# RobotControlBoard.net
KiCad netlist of a schematic drawn in EAGLE
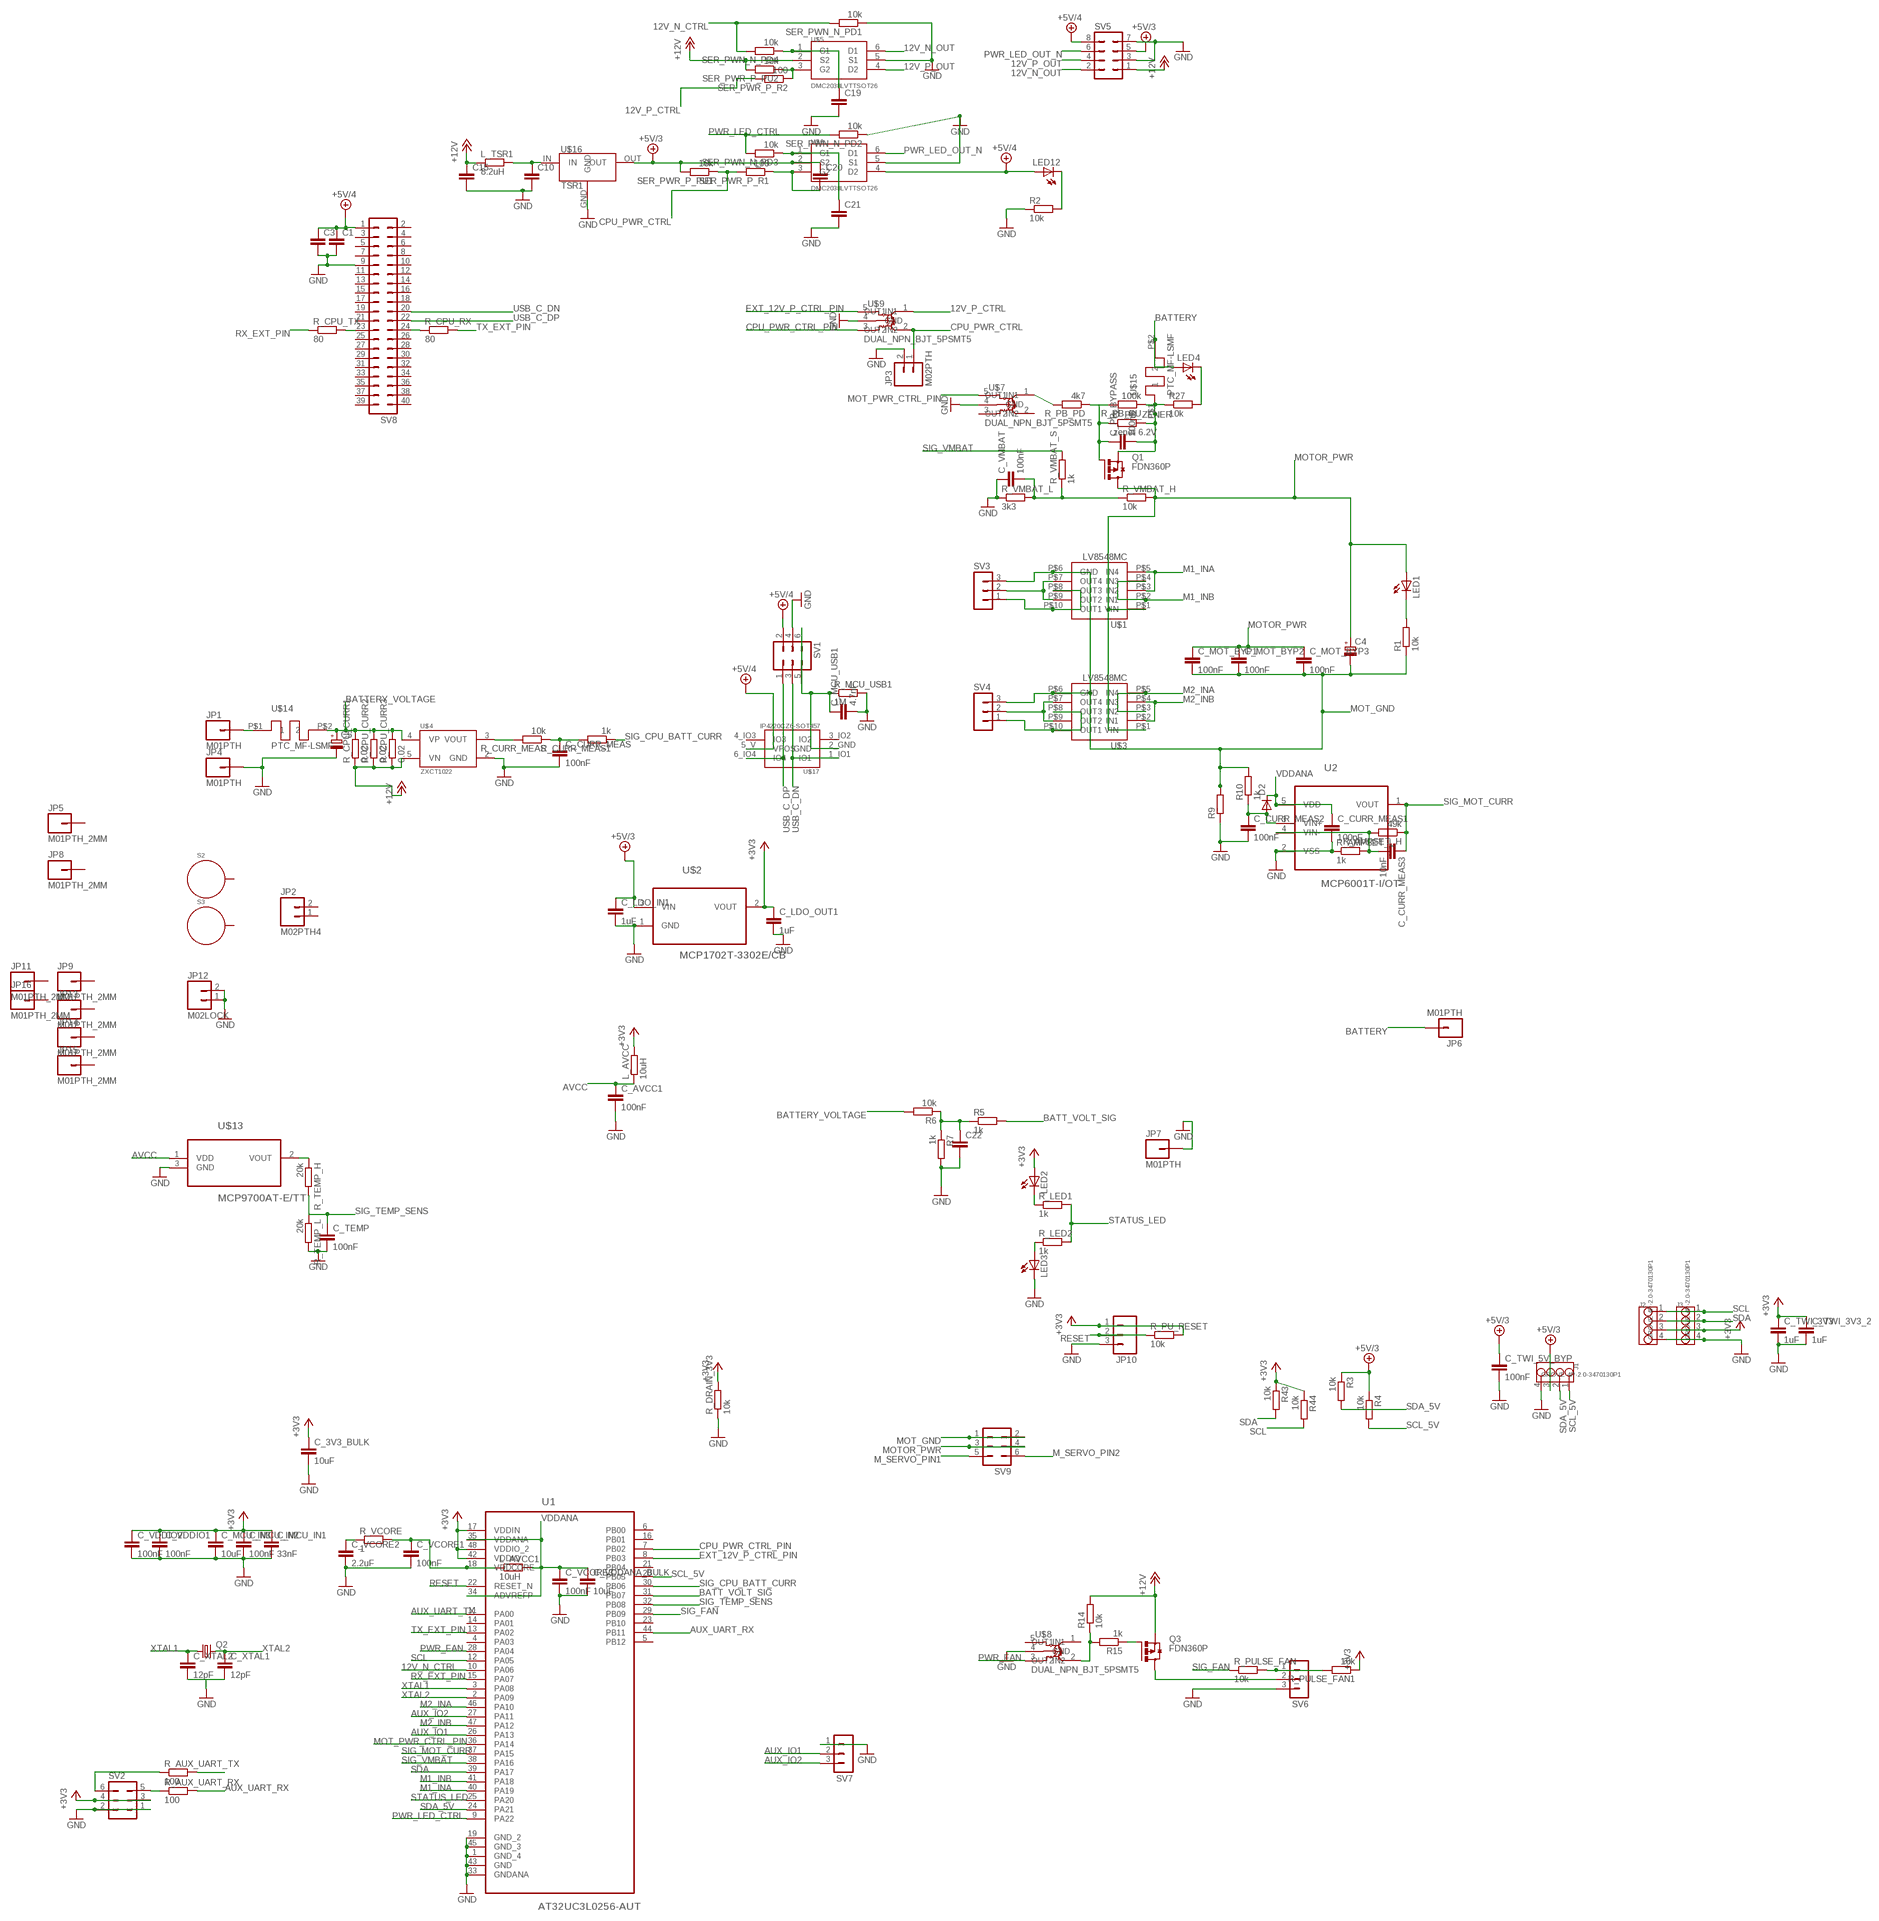
[diagram p0: schematic, sheet 1]

(export (version "E")
  (design (tool "Eeschema 10.0.6"))
  (components
    (comp (ref "C1")
      (value "C-EUC1210K")
      (footprint "eagle-import:C1210K")
      (libsource (lib "eagle-import") (part "C-EUC1210K"))
    )
    (comp (ref "C3")
      (value "C-EUC1210K")
      (footprint "eagle-import:C1210K")
      (libsource (lib "eagle-import") (part "C-EUC1210K"))
    )
    (comp (ref "C4")
      (value "CPOL-EUE3.5-8")
      (footprint "eagle-import:E3,5-8")
      (libsource (lib "eagle-import") (part "CPOL-EUE3.5-8"))
    )
    (comp (ref "C5")
      (value "CPOL-EUE2.5-6")
      (footprint "eagle-import:E2,5-6")
      (libsource (lib "eagle-import") (part "CPOL-EUE2.5-6"))
    )
    (comp (ref "C10")
      (value "C-EUC0805")
      (footprint "eagle-import:C0805")
      (libsource (lib "eagle-import") (part "C-EUC0805"))
    )
    (comp (ref "C15")
      (value "C-EUC0805")
      (footprint "eagle-import:C0805")
      (libsource (lib "eagle-import") (part "C-EUC0805"))
    )
    (comp (ref "C19")
      (value "C-EUC0603K")
      (footprint "eagle-import:C0603K")
      (libsource (lib "eagle-import") (part "C-EUC0603K"))
    )
    (comp (ref "C20")
      (value "C-EUC0603K")
      (footprint "eagle-import:C0603K")
      (libsource (lib "eagle-import") (part "C-EUC0603K"))
    )
    (comp (ref "C21")
      (value "C-EUC0603K")
      (footprint "eagle-import:C0603K")
      (libsource (lib "eagle-import") (part "C-EUC0603K"))
    )
    (comp (ref "C22")
      (value "C-EUC0603K")
      (footprint "eagle-import:C0603K")
      (libsource (lib "eagle-import") (part "C-EUC0603K"))
    )
    (comp (ref "C_3V3_BULK")
      (value "10uF")
      (footprint "eagle-import:C1206")
      (libsource (lib "eagle-import") (part "C-EUC1206"))
    )
    (comp (ref "C_AVCC1")
      (value "100nF")
      (footprint "eagle-import:C0603")
      (libsource (lib "eagle-import") (part "C-EUC0603"))
    )
    (comp (ref "C_CURR_MEAS")
      (value "100nF")
      (footprint "eagle-import:C0603K")
      (libsource (lib "eagle-import") (part "C-EUC0603K"))
    )
    (comp (ref "C_CURR_MEAS1")
      (value "100nF")
      (footprint "eagle-import:C0603K")
      (libsource (lib "eagle-import") (part "C-EUC0603K"))
    )
    (comp (ref "C_CURR_MEAS2")
      (value "100nF")
      (footprint "eagle-import:C0603K")
      (libsource (lib "eagle-import") (part "C-EUC0603K"))
    )
    (comp (ref "C_CURR_MEAS3")
      (value "10nF")
      (footprint "eagle-import:C0603K")
      (libsource (lib "eagle-import") (part "C-EUC0603K"))
    )
    (comp (ref "C_LDO_IN1")
      (value "1uF")
      (footprint "eagle-import:C0805")
      (libsource (lib "eagle-import") (part "C-EUC0805"))
    )
    (comp (ref "C_LDO_OUT1")
      (value "1uF")
      (footprint "eagle-import:C0805")
      (libsource (lib "eagle-import") (part "C-EUC0805"))
    )
    (comp (ref "C_MCU_IN1")
      (value "33nF")
      (footprint "eagle-import:C0603K")
      (libsource (lib "eagle-import") (part "C-EUC0603K"))
    )
    (comp (ref "C_MCU_IN2")
      (value "100nF")
      (footprint "eagle-import:C0603K")
      (libsource (lib "eagle-import") (part "C-EUC0603K"))
    )
    (comp (ref "C_MCU_IN3")
      (value "10uF")
      (footprint "eagle-import:C0805")
      (libsource (lib "eagle-import") (part "C-EUC0805"))
    )
    (comp (ref "C_MCU_USB1")
      (value "4.7nF")
      (footprint "eagle-import:C0603")
      (libsource (lib "eagle-import") (part "C-EUC0603"))
    )
    (comp (ref "C_MOT_BYP1")
      (value "100nF")
      (footprint "eagle-import:C0603K")
      (libsource (lib "eagle-import") (part "C-EUC0603K"))
    )
    (comp (ref "C_MOT_BYP2")
      (value "100nF")
      (footprint "eagle-import:C0603K")
      (libsource (lib "eagle-import") (part "C-EUC0603K"))
    )
    (comp (ref "C_MOT_BYP3")
      (value "100nF")
      (footprint "eagle-import:C0603K")
      (libsource (lib "eagle-import") (part "C-EUC0603K"))
    )
    (comp (ref "C_PB_BYPASS")
      (value "100nF")
      (footprint "eagle-import:C0603K")
      (libsource (lib "eagle-import") (part "C-EUC0603K"))
    )
    (comp (ref "C_TEMP")
      (value "100nF")
      (footprint "eagle-import:C0603")
      (libsource (lib "eagle-import") (part "C-EUC0603"))
    )
    (comp (ref "C_TWI_3V3")
      (value "1uF")
      (footprint "eagle-import:C0805K")
      (libsource (lib "eagle-import") (part "C-EUC0805K"))
    )
    (comp (ref "C_TWI_3V3_2")
      (value "1uF")
      (footprint "eagle-import:C0805K")
      (libsource (lib "eagle-import") (part "C-EUC0805K"))
    )
    (comp (ref "C_TWI_5V_BYP")
      (value "100nF")
      (footprint "eagle-import:C0603K")
      (libsource (lib "eagle-import") (part "C-EUC0603K"))
    )
    (comp (ref "C_VCORE1")
      (value "100nF")
      (footprint "eagle-import:C0603K")
      (libsource (lib "eagle-import") (part "C-EUC0603K"))
    )
    (comp (ref "C_VCORE2")
      (value "2.2uF")
      (footprint "eagle-import:C0805")
      (libsource (lib "eagle-import") (part "C-EUC0805"))
    )
    (comp (ref "C_VCORE3")
      (value "100nF")
      (footprint "eagle-import:C0603K")
      (libsource (lib "eagle-import") (part "C-EUC0603K"))
    )
    (comp (ref "C_VDDANA_BULK")
      (value "10uF")
      (footprint "eagle-import:C0805")
      (libsource (lib "eagle-import") (part "C-EUC0805"))
    )
    (comp (ref "C_VDDIO1")
      (value "100nF")
      (footprint "eagle-import:C0603K")
      (libsource (lib "eagle-import") (part "C-EUC0603K"))
    )
    (comp (ref "C_VDDIO2")
      (value "100nF")
      (footprint "eagle-import:C0603K")
      (libsource (lib "eagle-import") (part "C-EUC0603K"))
    )
    (comp (ref "C_VMBAT")
      (value "100nF")
      (footprint "eagle-import:C0603K")
      (libsource (lib "eagle-import") (part "C-EUC0603K"))
    )
    (comp (ref "C_XTAL1")
      (value "12pF")
      (footprint "eagle-import:C0603K")
      (libsource (lib "eagle-import") (part "C-EUC0603K"))
    )
    (comp (ref "C_XTAL2")
      (value "12pF")
      (footprint "eagle-import:C0603K")
      (libsource (lib "eagle-import") (part "C-EUC0603K"))
    )
    (comp (ref "D2")
      (value "DIODE-SOD323-W")
      (footprint "eagle-import:SOD323-W")
      (libsource (lib "eagle-import") (part "DIODE-SOD323-W"))
    )
    (comp (ref "D_PB_ZENER")
      (value "zener 6.2V")
      (footprint "eagle-import:R0805W")
      (libsource (lib "eagle-import") (part "R-EU_R0805W"))
    )
    (comp (ref "J1")
      (value "GROVE-4P-2.0-3470130P1")
      (footprint "eagle-import:4P-2.0")
      (libsource (lib "eagle-import") (part "GROVE-4P-2.0-3470130P1"))
    )
    (comp (ref "J2")
      (value "GROVE-4P-2.0-3470130P1")
      (footprint "eagle-import:4P-2.0")
      (libsource (lib "eagle-import") (part "GROVE-4P-2.0-3470130P1"))
    )
    (comp (ref "J3")
      (value "GROVE-4P-2.0-3470130P1")
      (footprint "eagle-import:4P-2.0")
      (libsource (lib "eagle-import") (part "GROVE-4P-2.0-3470130P1"))
    )
    (comp (ref "JP1")
      (value "M01PTH")
      (footprint "eagle-import:1X01")
      (libsource (lib "eagle-import") (part "M01PTH"))
    )
    (comp (ref "JP2")
      (value "M02PTH4")
      (footprint "eagle-import:1X02_XTRA_BIG")
      (libsource (lib "eagle-import") (part "M02PTH4"))
    )
    (comp (ref "JP3")
      (value "M02PTH")
      (footprint "eagle-import:1X02")
      (libsource (lib "eagle-import") (part "M02PTH"))
    )
    (comp (ref "JP4")
      (value "M01PTH")
      (footprint "eagle-import:1X01")
      (libsource (lib "eagle-import") (part "M01PTH"))
    )
    (comp (ref "JP5")
      (value "M01PTH_2MM")
      (footprint "eagle-import:1X01_2MM")
      (libsource (lib "eagle-import") (part "M01PTH_2MM"))
    )
    (comp (ref "JP6")
      (value "M01PTH")
      (footprint "eagle-import:1X01")
      (libsource (lib "eagle-import") (part "M01PTH"))
    )
    (comp (ref "JP7")
      (value "M01PTH")
      (footprint "eagle-import:1X01")
      (libsource (lib "eagle-import") (part "M01PTH"))
    )
    (comp (ref "JP8")
      (value "M01PTH_2MM")
      (footprint "eagle-import:1X01_2MM")
      (libsource (lib "eagle-import") (part "M01PTH_2MM"))
    )
    (comp (ref "JP9")
      (value "M01PTH_2MM")
      (footprint "eagle-import:1X01_2MM")
      (libsource (lib "eagle-import") (part "M01PTH_2MM"))
    )
    (comp (ref "JP10")
      (value "M03PTH")
      (footprint "eagle-import:1X03")
      (libsource (lib "eagle-import") (part "M03PTH"))
    )
    (comp (ref "JP11")
      (value "M01PTH_2MM")
      (footprint "eagle-import:1X01_2MM")
      (libsource (lib "eagle-import") (part "M01PTH_2MM"))
    )
    (comp (ref "JP12")
      (value "M02LOCK")
      (footprint "eagle-import:1X02_LOCK")
      (libsource (lib "eagle-import") (part "M02LOCK"))
    )
    (comp (ref "JP13")
      (value "M01PTH_2MM")
      (footprint "eagle-import:1X01_2MM")
      (libsource (lib "eagle-import") (part "M01PTH_2MM"))
    )
    (comp (ref "JP14")
      (value "M01PTH_2MM")
      (footprint "eagle-import:1X01_2MM")
      (libsource (lib "eagle-import") (part "M01PTH_2MM"))
    )
    (comp (ref "JP15")
      (value "M01PTH_2MM")
      (footprint "eagle-import:1X01_2MM")
      (libsource (lib "eagle-import") (part "M01PTH_2MM"))
    )
    (comp (ref "JP16")
      (value "M01PTH_2MM")
      (footprint "eagle-import:1X01_2MM")
      (libsource (lib "eagle-import") (part "M01PTH_2MM"))
    )
    (comp (ref "LED1")
      (value "LEDSML0603")
      (footprint "eagle-import:SML0603")
      (libsource (lib "eagle-import") (part "LEDSML0603"))
    )
    (comp (ref "LED2")
      (value "LEDSML0603")
      (footprint "eagle-import:SML0603")
      (libsource (lib "eagle-import") (part "LEDSML0603"))
    )
    (comp (ref "LED3")
      (value "LEDSML0603")
      (footprint "eagle-import:SML0603")
      (libsource (lib "eagle-import") (part "LEDSML0603"))
    )
    (comp (ref "LED4")
      (value "LEDSML0603")
      (footprint "eagle-import:SML0603")
      (libsource (lib "eagle-import") (part "LEDSML0603"))
    )
    (comp (ref "LED12")
      (value "LEDSML0603")
      (footprint "eagle-import:SML0603")
      (libsource (lib "eagle-import") (part "LEDSML0603"))
    )
    (comp (ref "L_AVCC")
      (value "10uH")
      (footprint "eagle-import:R0603")
      (libsource (lib "eagle-import") (part "R-EU_R0603"))
    )
    (comp (ref "L_AVCC1")
      (value "10uH")
      (footprint "eagle-import:R0805")
      (libsource (lib "eagle-import") (part "R-EU_R0805"))
    )
    (comp (ref "L_TSR1")
      (value "8.2uH")
      (footprint "eagle-import:M0805")
      (libsource (lib "eagle-import") (part "R-EU_M0805"))
    )
    (comp (ref "Q1")
      (value "FDN360P")
      (footprint "eagle-import:SUPER-SOT3")
      (libsource (lib "eagle-import") (part "FDN360P"))
    )
    (comp (ref "Q2")
      (value "CRYSTALHC49S")
      (footprint "eagle-import:HC49_S")
      (libsource (lib "eagle-import") (part "CRYSTALHC49S"))
    )
    (comp (ref "Q3")
      (value "FDN360P")
      (footprint "eagle-import:SUPER-SOT3")
      (libsource (lib "eagle-import") (part "FDN360P"))
    )
    (comp (ref "R1")
      (value "10k")
      (footprint "eagle-import:R0603")
      (libsource (lib "eagle-import") (part "R-EU_R0603"))
    )
    (comp (ref "R2")
      (value "10k")
      (footprint "eagle-import:R0603")
      (libsource (lib "eagle-import") (part "R-EU_R0603"))
    )
    (comp (ref "R3")
      (value "10k")
      (footprint "eagle-import:R0603")
      (libsource (lib "eagle-import") (part "R-EU_R0603"))
    )
    (comp (ref "R4")
      (value "10k")
      (footprint "eagle-import:R0603")
      (libsource (lib "eagle-import") (part "R-EU_R0603"))
    )
    (comp (ref "R5")
      (value "1k")
      (footprint "eagle-import:R0603")
      (libsource (lib "eagle-import") (part "R-EU_R0603"))
    )
    (comp (ref "R6")
      (value "10k")
      (footprint "eagle-import:R0603")
      (libsource (lib "eagle-import") (part "R-EU_R0603"))
    )
    (comp (ref "R7")
      (value "1k")
      (footprint "eagle-import:R0603")
      (libsource (lib "eagle-import") (part "R-EU_R0603"))
    )
    (comp (ref "R9")
      (value "R-EU_M1206")
      (footprint "eagle-import:M1206")
      (libsource (lib "eagle-import") (part "R-EU_M1206"))
    )
    (comp (ref "R10")
      (value "1k")
      (footprint "eagle-import:R0603")
      (libsource (lib "eagle-import") (part "R-EU_R0603"))
    )
    (comp (ref "R14")
      (value "10k")
      (footprint "eagle-import:R0603")
      (libsource (lib "eagle-import") (part "R-EU_R0603"))
    )
    (comp (ref "R15")
      (value "1k")
      (footprint "eagle-import:R0603")
      (libsource (lib "eagle-import") (part "R-EU_R0603"))
    )
    (comp (ref "R27")
      (value "10k")
      (footprint "eagle-import:R0603")
      (libsource (lib "eagle-import") (part "R-EU_R0603"))
    )
    (comp (ref "R43")
      (value "10k")
      (footprint "eagle-import:R0603")
      (libsource (lib "eagle-import") (part "R-EU_R0603"))
    )
    (comp (ref "R44")
      (value "10k")
      (footprint "eagle-import:R0603")
      (libsource (lib "eagle-import") (part "R-EU_R0603"))
    )
    (comp (ref "R_AMPSET_H")
      (value "49k")
      (footprint "eagle-import:R0603")
      (libsource (lib "eagle-import") (part "R-EU_R0603"))
    )
    (comp (ref "R_AMPSET_L")
      (value "1k")
      (footprint "eagle-import:R0603")
      (libsource (lib "eagle-import") (part "R-EU_R0603"))
    )
    (comp (ref "R_AUX_UART_RX")
      (value "100")
      (footprint "eagle-import:R0603")
      (libsource (lib "eagle-import") (part "R-EU_R0603"))
    )
    (comp (ref "R_AUX_UART_TX")
      (value "100")
      (footprint "eagle-import:R0603")
      (libsource (lib "eagle-import") (part "R-EU_R0603"))
    )
    (comp (ref "R_CPU_CURR1")
      (value "0.02")
      (footprint "eagle-import:R0805")
      (libsource (lib "eagle-import") (part "R-EU_R0805"))
    )
    (comp (ref "R_CPU_CURR2")
      (value "0.02")
      (footprint "eagle-import:R0805")
      (libsource (lib "eagle-import") (part "R-EU_R0805"))
    )
    (comp (ref "R_CPU_CURR3")
      (value "0.02")
      (footprint "eagle-import:R0805")
      (libsource (lib "eagle-import") (part "R-EU_R0805"))
    )
    (comp (ref "R_CPU_RX")
      (value "80")
      (footprint "eagle-import:R0603")
      (libsource (lib "eagle-import") (part "R-EU_R0603"))
    )
    (comp (ref "R_CPU_TX")
      (value "80")
      (footprint "eagle-import:R0603")
      (libsource (lib "eagle-import") (part "R-EU_R0603"))
    )
    (comp (ref "R_CURR_MEAS")
      (value "10k")
      (footprint "eagle-import:R0603")
      (libsource (lib "eagle-import") (part "R-EU_R0603"))
    )
    (comp (ref "R_CURR_MEAS1")
      (value "1k")
      (footprint "eagle-import:R0603")
      (libsource (lib "eagle-import") (part "R-EU_R0603"))
    )
    (comp (ref "R_DRAIN_3V3")
      (value "10k")
      (footprint "eagle-import:R0603")
      (libsource (lib "eagle-import") (part "R-EU_R0603"))
    )
    (comp (ref "R_LED1")
      (value "1k")
      (footprint "eagle-import:R0603")
      (libsource (lib "eagle-import") (part "R-EU_R0603"))
    )
    (comp (ref "R_LED2")
      (value "1k")
      (footprint "eagle-import:R0603")
      (libsource (lib "eagle-import") (part "R-EU_R0603"))
    )
    (comp (ref "R_MCU_USB1")
      (value "1M")
      (footprint "eagle-import:R0603")
      (libsource (lib "eagle-import") (part "R-EU_R0603"))
    )
    (comp (ref "R_PB_PD")
      (value "4k7")
      (footprint "eagle-import:R0603")
      (libsource (lib "eagle-import") (part "R-EU_R0603"))
    )
    (comp (ref "R_PB_PU")
      (value "100k")
      (footprint "eagle-import:R0603")
      (libsource (lib "eagle-import") (part "R-EU_R0603"))
    )
    (comp (ref "R_PULSE_FAN")
      (value "10k")
      (footprint "eagle-import:R0603")
      (libsource (lib "eagle-import") (part "R-EU_R0603"))
    )
    (comp (ref "R_PULSE_FAN1")
      (value "10k")
      (footprint "eagle-import:R0603")
      (libsource (lib "eagle-import") (part "R-EU_R0603"))
    )
    (comp (ref "R_PU_RESET")
      (value "10k")
      (footprint "eagle-import:R0603")
      (libsource (lib "eagle-import") (part "R-EU_R0603"))
    )
    (comp (ref "R_TEMP_H")
      (value "20k")
      (footprint "eagle-import:R0603")
      (libsource (lib "eagle-import") (part "R-EU_R0603"))
    )
    (comp (ref "R_TEMP_L")
      (value "20k")
      (footprint "eagle-import:R0603")
      (libsource (lib "eagle-import") (part "R-EU_R0603"))
    )
    (comp (ref "R_VCORE")
      (value "1")
      (footprint "eagle-import:R0603")
      (libsource (lib "eagle-import") (part "R-EU_R0603"))
    )
    (comp (ref "R_VMBAT_H")
      (value "10k")
      (footprint "eagle-import:R0603")
      (libsource (lib "eagle-import") (part "R-EU_R0603"))
    )
    (comp (ref "R_VMBAT_L")
      (value "3k3")
      (footprint "eagle-import:R0603")
      (libsource (lib "eagle-import") (part "R-EU_R0603"))
    )
    (comp (ref "R_VMBAT_S")
      (value "1k")
      (footprint "eagle-import:R0603")
      (libsource (lib "eagle-import") (part "R-EU_R0603"))
    )
    (comp (ref "S2")
      (value "STANDOFF_ELECTRICAL")
      (footprint "eagle-import:STANDOFF-ELECTRICAL")
      (libsource (lib "eagle-import") (part "STANDOFF_ELECTRICAL"))
    )
    (comp (ref "S3")
      (value "STANDOFF_ELECTRICAL")
      (footprint "eagle-import:STANDOFF-ELECTRICAL")
      (libsource (lib "eagle-import") (part "STANDOFF_ELECTRICAL"))
    )
    (comp (ref "SER_PWN_N_PD1")
      (value "10k")
      (footprint "eagle-import:R0603")
      (libsource (lib "eagle-import") (part "R-EU_R0603"))
    )
    (comp (ref "SER_PWN_N_PD2")
      (value "10k")
      (footprint "eagle-import:R0603")
      (libsource (lib "eagle-import") (part "R-EU_R0603"))
    )
    (comp (ref "SER_PWN_N_PD3")
      (value "10k")
      (footprint "eagle-import:R0603")
      (libsource (lib "eagle-import") (part "R-EU_R0603"))
    )
    (comp (ref "SER_PWN_N_PD4")
      (value "10k")
      (footprint "eagle-import:R0603")
      (libsource (lib "eagle-import") (part "R-EU_R0603"))
    )
    (comp (ref "SER_PWR_P_PU1")
      (value "10k")
      (footprint "eagle-import:R0603")
      (libsource (lib "eagle-import") (part "R-EU_R0603"))
    )
    (comp (ref "SER_PWR_P_PU2")
      (value "10k")
      (footprint "eagle-import:R0603")
      (libsource (lib "eagle-import") (part "R-EU_R0603"))
    )
    (comp (ref "SER_PWR_P_R1")
      (value "100")
      (footprint "eagle-import:R0603")
      (libsource (lib "eagle-import") (part "R-EU_R0603"))
    )
    (comp (ref "SER_PWR_P_R2")
      (value "100")
      (footprint "eagle-import:R0603")
      (libsource (lib "eagle-import") (part "R-EU_R0603"))
    )
    (comp (ref "SV1")
      (value "MA03-2")
      (footprint "eagle-import:MA03-2")
      (libsource (lib "eagle-import") (part "MA03-2"))
    )
    (comp (ref "SV2")
      (value "MA03-2")
      (footprint "eagle-import:MA03-2")
      (libsource (lib "eagle-import") (part "MA03-2"))
    )
    (comp (ref "SV3")
      (value "MA03-1")
      (footprint "eagle-import:MA03-1")
      (libsource (lib "eagle-import") (part "MA03-1"))
    )
    (comp (ref "SV4")
      (value "MA03-1")
      (footprint "eagle-import:MA03-1")
      (libsource (lib "eagle-import") (part "MA03-1"))
    )
    (comp (ref "SV5")
      (value "MA04-2")
      (footprint "eagle-import:MA04-2")
      (libsource (lib "eagle-import") (part "MA04-2"))
    )
    (comp (ref "SV6")
      (value "MA03-1")
      (footprint "eagle-import:MA03-1")
      (libsource (lib "eagle-import") (part "MA03-1"))
    )
    (comp (ref "SV7")
      (value "MA03-1")
      (footprint "eagle-import:MA03-1")
      (libsource (lib "eagle-import") (part "MA03-1"))
    )
    (comp (ref "SV8")
      (value "MA20-2")
      (footprint "eagle-import:MA20-2")
      (libsource (lib "eagle-import") (part "MA20-2"))
    )
    (comp (ref "SV9")
      (value "MA03-2")
      (footprint "eagle-import:MA03-2")
      (libsource (lib "eagle-import") (part "MA03-2"))
    )
    (comp (ref "U$1")
      (value "LV8548MC")
      (footprint "eagle-import:SOIC10")
      (libsource (lib "eagle-import") (part "LV8548MC"))
    )
    (comp (ref "U$2")
      (value "MCP1702T-3302E/CB")
      (footprint "eagle-import:SOT95P255X145-3N")
      (libsource (lib "eagle-import") (part "MCP1702T-3302E/CB"))
    )
    (comp (ref "U$3")
      (value "LV8548MC")
      (footprint "eagle-import:SOIC10")
      (libsource (lib "eagle-import") (part "LV8548MC"))
    )
    (comp (ref "U$4")
      (value "ZXCT1022")
      (footprint "eagle-import:SOT23-5")
      (libsource (lib "eagle-import") (part "ZXCT1022"))
    )
    (comp (ref "U$5")
      (value "DMC2038LVTTSOT26")
      (footprint "eagle-import:TSOT26")
      (libsource (lib "eagle-import") (part "DMC2038LVTTSOT26"))
    )
    (comp (ref "U$6")
      (value "DMC2038LVTTSOT26")
      (footprint "eagle-import:TSOT26")
      (libsource (lib "eagle-import") (part "DMC2038LVTTSOT26"))
    )
    (comp (ref "U$7")
      (value "DUAL_NPN_BJT_5PSMT5")
      (footprint "eagle-import:SC-74A")
      (libsource (lib "eagle-import") (part "DUAL_NPN_BJT_5PSMT5"))
    )
    (comp (ref "U$8")
      (value "DUAL_NPN_BJT_5PSMT5")
      (footprint "eagle-import:SC-74A")
      (libsource (lib "eagle-import") (part "DUAL_NPN_BJT_5PSMT5"))
    )
    (comp (ref "U$9")
      (value "DUAL_NPN_BJT_5PSMT5")
      (footprint "eagle-import:SC-74A")
      (libsource (lib "eagle-import") (part "DUAL_NPN_BJT_5PSMT5"))
    )
    (comp (ref "U$13")
      (value "MCP9700AT-E/TT")
      (footprint "eagle-import:SOT95P237X112-3N")
      (libsource (lib "eagle-import") (part "MCP9700AT-E/TT"))
    )
    (comp (ref "U$14")
      (value "PTC_MF-LSMF")
      (footprint "eagle-import:PTC_FUSE_BOURNS")
      (libsource (lib "eagle-import") (part "PTC_MF-LSMF"))
    )
    (comp (ref "U$15")
      (value "PTC_MF-LSMF")
      (footprint "eagle-import:PTC_FUSE_BOURNS")
      (libsource (lib "eagle-import") (part "PTC_MF-LSMF"))
    )
    (comp (ref "U$16")
      (value "TSR1")
      (footprint "eagle-import:TSR-1")
      (libsource (lib "eagle-import") (part "TSR1"))
    )
    (comp (ref "U$17")
      (value "IP4220CZ6-SOT457")
      (footprint "eagle-import:SOT457_NXP_ESD")
      (libsource (lib "eagle-import") (part "IP4220CZ6-SOT457"))
    )
    (comp (ref "U1")
      (value "AT32UC3L0256-AUT")
      (footprint "eagle-import:QFP50P900X900X120-48N")
      (libsource (lib "eagle-import") (part "AT32UC3L0256-AUT"))
    )
    (comp (ref "U2")
      (value "MCP6001T-I/OT")
      (footprint "eagle-import:SOT95P270X145-5N")
      (libsource (lib "eagle-import") (part "MCP6001T-I/OT"))
    )
  )
  (nets
    (net (code "1") (name "+3V3") (class "Default")
      (node (ref "C_3V3_BULK") (pin "1") (pinfunction "1_1") (pintype "passive"))
      (node (ref "C_LDO_OUT1") (pin "1") (pinfunction "1_1") (pintype "passive"))
      (node (ref "C_MCU_IN1") (pin "1") (pinfunction "1_1") (pintype "passive"))
      (node (ref "C_MCU_IN2") (pin "1") (pinfunction "1_1") (pintype "passive"))
      (node (ref "C_MCU_IN3") (pin "1") (pinfunction "1_1") (pintype "passive"))
      (node (ref "C_TWI_3V3") (pin "1") (pinfunction "1_1") (pintype "passive"))
      (node (ref "C_TWI_3V3_2") (pin "1") (pinfunction "1_1") (pintype "passive"))
      (node (ref "C_VDDIO1") (pin "1") (pinfunction "1_1") (pintype "passive"))
      (node (ref "C_VDDIO2") (pin "1") (pinfunction "1_1") (pintype "passive"))
      (node (ref "J2") (pin "3") (pinfunction "3_3") (pintype "bidirectional"))
      (node (ref "J3") (pin "3") (pinfunction "3_3") (pintype "bidirectional"))
      (node (ref "JP10") (pin "1") (pinfunction "1_1") (pintype "passive"))
      (node (ref "LED2") (pin "A") (pinfunction "A_A") (pintype "passive"))
      (node (ref "L_AVCC") (pin "2") (pinfunction "2_2") (pintype "passive"))
      (node (ref "R43") (pin "1") (pinfunction "1_1") (pintype "passive"))
      (node (ref "R44") (pin "1") (pinfunction "1_1") (pintype "passive"))
      (node (ref "R_DRAIN_3V3") (pin "2") (pinfunction "2_2") (pintype "passive"))
      (node (ref "R_PULSE_FAN1") (pin "1") (pinfunction "1_1") (pintype "passive"))
      (node (ref "R_PU_RESET") (pin "2") (pinfunction "2_2") (pintype "passive"))
      (node (ref "SV2") (pin "3") (pinfunction "3_3") (pintype "passive"))
      (node (ref "SV2") (pin "4") (pinfunction "4_4") (pintype "passive"))
      (node (ref "U$2") (pin "2") (pinfunction "VOUT_2") (pintype "output"))
      (node (ref "U1") (pin "17") (pinfunction "VDDIN_17") (pintype "power_in"))
      (node (ref "U1") (pin "42") (pinfunction "VDDIO_42") (pintype "power_in"))
      (node (ref "U1") (pin "48") (pinfunction "VDDIO_2_48") (pintype "power_in"))
    )
    (net (code "2") (name "+5V{slash}3") (class "Default")
      (node (ref "C20") (pin "1") (pinfunction "1_1") (pintype "passive"))
      (node (ref "C_LDO_IN1") (pin "1") (pinfunction "1_1") (pintype "passive"))
      (node (ref "C_TWI_5V_BYP") (pin "1") (pinfunction "1_1") (pintype "passive"))
      (node (ref "J1") (pin "3") (pinfunction "3_3") (pintype "bidirectional"))
      (node (ref "R3") (pin "1") (pinfunction "1_1") (pintype "passive"))
      (node (ref "R4") (pin "1") (pinfunction "1_1") (pintype "passive"))
      (node (ref "SER_PWR_P_PU1") (pin "2") (pinfunction "2_2") (pintype "passive"))
      (node (ref "SV5") (pin "5") (pinfunction "5_5") (pintype "passive"))
      (node (ref "U$16") (pin "OUT") (pinfunction "OUT_OUT") (pintype "bidirectional"))
      (node (ref "U$2") (pin "3") (pinfunction "VIN_3") (pintype "input"))
      (node (ref "U$6") (pin "2") (pinfunction "S2_2") (pintype "bidirectional"))
    )
    (net (code "3") (name "+5V{slash}4") (class "Default")
      (node (ref "C1") (pin "1") (pinfunction "1_1") (pintype "passive"))
      (node (ref "C3") (pin "1") (pinfunction "1_1") (pintype "passive"))
      (node (ref "LED12") (pin "A") (pinfunction "A_A") (pintype "passive"))
      (node (ref "SV1") (pin "2") (pinfunction "2_2") (pintype "passive"))
      (node (ref "SV5") (pin "8") (pinfunction "8_8") (pintype "passive"))
      (node (ref "SV8") (pin "1") (pinfunction "1_1") (pintype "passive"))
      (node (ref "U$17") (pin "5_V") (pinfunction "VPOS_5_V") (pintype "bidirectional"))
      (node (ref "U$6") (pin "4") (pinfunction "D2_4") (pintype "bidirectional"))
    )
    (net (code "4") (name "+12V") (class "Default")
      (node (ref "C15") (pin "1") (pinfunction "1_1") (pintype "passive"))
      (node (ref "L_TSR1") (pin "1") (pinfunction "1_1") (pintype "passive"))
      (node (ref "Q3") (pin "2") (pinfunction "S_2") (pintype "passive"))
      (node (ref "R14") (pin "2") (pinfunction "2_2") (pintype "passive"))
      (node (ref "R_CPU_CURR1") (pin "1") (pinfunction "1_1") (pintype "passive"))
      (node (ref "R_CPU_CURR2") (pin "1") (pinfunction "1_1") (pintype "passive"))
      (node (ref "R_CPU_CURR3") (pin "1") (pinfunction "1_1") (pintype "passive"))
      (node (ref "SER_PWR_P_PU2") (pin "2") (pinfunction "2_2") (pintype "passive"))
      (node (ref "SV5") (pin "1") (pinfunction "1_1") (pintype "passive"))
      (node (ref "U$4") (pin "5") (pinfunction "VN_5") (pintype "bidirectional"))
      (node (ref "U$5") (pin "2") (pinfunction "S2_2") (pintype "bidirectional"))
    )
    (net (code "5") (name "/12V_N_CTRL") (class "Default")
      (node (ref "SER_PWN_N_PD1") (pin "2") (pinfunction "2_2") (pintype "passive"))
      (node (ref "SER_PWN_N_PD4") (pin "2") (pinfunction "2_2") (pintype "passive"))
      (node (ref "U1") (pin "10") (pinfunction "PA06_10") (pintype "bidirectional"))
    )
    (net (code "6") (name "/12V_N_OUT") (class "Default")
      (node (ref "SV5") (pin "2") (pinfunction "2_2") (pintype "passive"))
      (node (ref "U$5") (pin "6") (pinfunction "D1_6") (pintype "bidirectional"))
    )
    (net (code "7") (name "/12V_P_CTRL") (class "Default")
      (node (ref "SER_PWR_P_R2") (pin "2") (pinfunction "2_2") (pintype "passive"))
      (node (ref "U$9") (pin "1") (pinfunction "OUT1_1") (pintype "bidirectional"))
    )
    (net (code "8") (name "/12V_P_OUT") (class "Default")
      (node (ref "SV5") (pin "4") (pinfunction "4_4") (pintype "passive"))
      (node (ref "U$5") (pin "4") (pinfunction "D2_4") (pintype "bidirectional"))
    )
    (net (code "9") (name "/AUX_IO1") (class "Default")
      (node (ref "SV7") (pin "2") (pinfunction "2_2") (pintype "passive"))
      (node (ref "U1") (pin "26") (pinfunction "PA13_26") (pintype "bidirectional"))
    )
    (net (code "10") (name "/AUX_IO2") (class "Default")
      (node (ref "SV7") (pin "3") (pinfunction "3_3") (pintype "passive"))
      (node (ref "U1") (pin "27") (pinfunction "PA11_27") (pintype "bidirectional"))
    )
    (net (code "11") (name "/AUX_UART_RX") (class "Default")
      (node (ref "R_AUX_UART_RX") (pin "2") (pinfunction "2_2") (pintype "passive"))
      (node (ref "U1") (pin "44") (pinfunction "PB11_44") (pintype "bidirectional"))
    )
    (net (code "12") (name "/AUX_UART_TX") (class "Default")
      (node (ref "R_AUX_UART_TX") (pin "2") (pinfunction "2_2") (pintype "passive"))
      (node (ref "U1") (pin "11") (pinfunction "PA00_11") (pintype "bidirectional"))
    )
    (net (code "13") (name "/AVCC") (class "Default")
      (node (ref "C_AVCC1") (pin "1") (pinfunction "1_1") (pintype "passive"))
      (node (ref "L_AVCC") (pin "1") (pinfunction "1_1") (pintype "passive"))
      (node (ref "U$13") (pin "1") (pinfunction "VDD_1") (pintype "power_in"))
    )
    (net (code "14") (name "/BATTERY") (class "Default")
      (node (ref "JP6") (pin "1") (pinfunction "1_1") (pintype "passive"))
      (node (ref "LED4") (pin "A") (pinfunction "A_A") (pintype "passive"))
      (node (ref "U$15") (pin "P$2") (pinfunction "2_P$2") (pintype "bidirectional"))
    )
    (net (code "15") (name "/BATTERY_VOLTAGE") (class "Default")
      (node (ref "C5") (pin "+") (pinfunction "+_+") (pintype "passive"))
      (node (ref "R6") (pin "2") (pinfunction "2_2") (pintype "passive"))
      (node (ref "R_CPU_CURR1") (pin "2") (pinfunction "2_2") (pintype "passive"))
      (node (ref "R_CPU_CURR2") (pin "2") (pinfunction "2_2") (pintype "passive"))
      (node (ref "R_CPU_CURR3") (pin "2") (pinfunction "2_2") (pintype "passive"))
      (node (ref "U$14") (pin "P$2") (pinfunction "2_P$2") (pintype "bidirectional"))
      (node (ref "U$4") (pin "4") (pinfunction "VP_4") (pintype "bidirectional"))
    )
    (net (code "16") (name "/BATT_VOLT_SIG") (class "Default")
      (node (ref "R5") (pin "2") (pinfunction "2_2") (pintype "passive"))
      (node (ref "U1") (pin "31") (pinfunction "PB07_31") (pintype "bidirectional"))
    )
    (net (code "17") (name "/CPU_PWR_CTRL") (class "Default")
      (node (ref "JP3") (pin "1") (pinfunction "1_1") (pintype "passive"))
      (node (ref "SER_PWR_P_PU1") (pin "1") (pinfunction "1_1") (pintype "passive"))
      (node (ref "SER_PWR_P_R1") (pin "2") (pinfunction "2_2") (pintype "passive"))
      (node (ref "U$9") (pin "2") (pinfunction "OUT2_2") (pintype "bidirectional"))
    )
    (net (code "18") (name "/CPU_PWR_CTRL_PIN") (class "Default")
      (node (ref "U$9") (pin "3") (pinfunction "IN2_3") (pintype "bidirectional"))
      (node (ref "U1") (pin "7") (pinfunction "PB02_7") (pintype "bidirectional"))
    )
    (net (code "19") (name "/EXT_12V_P_CTRL_PIN") (class "Default")
      (node (ref "U$9") (pin "5") (pinfunction "IN1_5") (pintype "bidirectional"))
      (node (ref "U1") (pin "8") (pinfunction "PB03_8") (pintype "bidirectional"))
    )
    (net (code "20") (name "/M1_INA") (class "Default")
      (node (ref "U$1") (pin "P$3") (pinfunction "IN2_P$3") (pintype "bidirectional"))
      (node (ref "U$1") (pin "P$5") (pinfunction "IN4_P$5") (pintype "bidirectional"))
      (node (ref "U1") (pin "40") (pinfunction "PA19_40") (pintype "bidirectional"))
    )
    (net (code "21") (name "/M1_INB") (class "Default")
      (node (ref "U$1") (pin "P$2") (pinfunction "IN1_P$2") (pintype "bidirectional"))
      (node (ref "U$1") (pin "P$4") (pinfunction "IN3_P$4") (pintype "bidirectional"))
      (node (ref "U1") (pin "41") (pinfunction "PA18_41") (pintype "bidirectional"))
    )
    (net (code "22") (name "/M2_INA") (class "Default")
      (node (ref "U$3") (pin "P$3") (pinfunction "IN2_P$3") (pintype "bidirectional"))
      (node (ref "U$3") (pin "P$5") (pinfunction "IN4_P$5") (pintype "bidirectional"))
      (node (ref "U1") (pin "46") (pinfunction "PA10_46") (pintype "bidirectional"))
    )
    (net (code "23") (name "/M2_INB") (class "Default")
      (node (ref "U$3") (pin "P$2") (pinfunction "IN1_P$2") (pintype "bidirectional"))
      (node (ref "U$3") (pin "P$4") (pinfunction "IN3_P$4") (pintype "bidirectional"))
      (node (ref "U1") (pin "47") (pinfunction "PA12_47") (pintype "bidirectional"))
    )
    (net (code "24") (name "/MOTOR_PWR") (class "Default")
      (node (ref "C4") (pin "+") (pinfunction "+_+") (pintype "passive"))
      (node (ref "C_MOT_BYP1") (pin "1") (pinfunction "1_1") (pintype "passive"))
      (node (ref "C_MOT_BYP2") (pin "1") (pinfunction "1_1") (pintype "passive"))
      (node (ref "C_MOT_BYP3") (pin "1") (pinfunction "1_1") (pintype "passive"))
      (node (ref "LED1") (pin "A") (pinfunction "A_A") (pintype "passive"))
      (node (ref "Q1") (pin "3") (pinfunction "D_3") (pintype "passive"))
      (node (ref "R_VMBAT_H") (pin "2") (pinfunction "2_2") (pintype "passive"))
      (node (ref "SV9") (pin "3") (pinfunction "3_3") (pintype "passive"))
      (node (ref "SV9") (pin "4") (pinfunction "4_4") (pintype "passive"))
      (node (ref "U$1") (pin "P$1") (pinfunction "VIN_P$1") (pintype "bidirectional"))
      (node (ref "U$3") (pin "P$1") (pinfunction "VIN_P$1") (pintype "bidirectional"))
    )
    (net (code "25") (name "/MOT_GND") (class "Default")
      (node (ref "C4") (pin "-") (pinfunction "-_-") (pintype "passive"))
      (node (ref "C_MOT_BYP1") (pin "2") (pinfunction "2_2") (pintype "passive"))
      (node (ref "C_MOT_BYP2") (pin "2") (pinfunction "2_2") (pintype "passive"))
      (node (ref "C_MOT_BYP3") (pin "2") (pinfunction "2_2") (pintype "passive"))
      (node (ref "R1") (pin "1") (pinfunction "1_1") (pintype "passive"))
      (node (ref "R10") (pin "2") (pinfunction "2_2") (pintype "passive"))
      (node (ref "R9") (pin "2") (pinfunction "2_2") (pintype "passive"))
      (node (ref "SV3") (pin "3") (pinfunction "3_3") (pintype "passive"))
      (node (ref "SV4") (pin "3") (pinfunction "3_3") (pintype "passive"))
      (node (ref "SV9") (pin "1") (pinfunction "1_1") (pintype "passive"))
      (node (ref "SV9") (pin "2") (pinfunction "2_2") (pintype "passive"))
      (node (ref "U$1") (pin "P$6") (pinfunction "GND_P$6") (pintype "bidirectional"))
      (node (ref "U$3") (pin "P$6") (pinfunction "GND_P$6") (pintype "bidirectional"))
    )
    (net (code "26") (name "/MOT_PWR_CTRL_PIN") (class "Default")
      (node (ref "U$7") (pin "5") (pinfunction "IN1_5") (pintype "bidirectional"))
      (node (ref "U1") (pin "36") (pinfunction "PA14_36") (pintype "bidirectional"))
    )
    (net (code "27") (name "/M_SERVO_PIN1") (class "Default")
      (node (ref "SV9") (pin "5") (pinfunction "5_5") (pintype "passive"))
    )
    (net (code "28") (name "/M_SERVO_PIN2") (class "Default")
      (node (ref "SV9") (pin "6") (pinfunction "6_6") (pintype "passive"))
    )
    (net (code "29") (name "/PWR_FAN") (class "Default")
      (node (ref "U$8") (pin "3") (pinfunction "IN2_3") (pintype "bidirectional"))
      (node (ref "U1") (pin "28") (pinfunction "PA04_28") (pintype "bidirectional"))
    )
    (net (code "30") (name "/PWR_LED_CTRL") (class "Default")
      (node (ref "SER_PWN_N_PD2") (pin "2") (pinfunction "2_2") (pintype "passive"))
      (node (ref "SER_PWN_N_PD3") (pin "2") (pinfunction "2_2") (pintype "passive"))
      (node (ref "U1") (pin "9") (pinfunction "PA22_9") (pintype "bidirectional"))
    )
    (net (code "31") (name "/PWR_LED_OUT_N") (class "Default")
      (node (ref "SV5") (pin "6") (pinfunction "6_6") (pintype "passive"))
      (node (ref "U$6") (pin "6") (pinfunction "D1_6") (pintype "bidirectional"))
    )
    (net (code "32") (name "/RESET") (class "Default")
      (node (ref "JP10") (pin "2") (pinfunction "2_2") (pintype "passive"))
      (node (ref "R_PU_RESET") (pin "1") (pinfunction "1_1") (pintype "passive"))
      (node (ref "U1") (pin "22") (pinfunction "RESET_N_22") (pintype "input"))
    )
    (net (code "33") (name "/RX_EXT_PIN") (class "Default")
      (node (ref "R_CPU_TX") (pin "1") (pinfunction "1_1") (pintype "passive"))
      (node (ref "U1") (pin "15") (pinfunction "PA07_15") (pintype "bidirectional"))
    )
    (net (code "34") (name "/SCL") (class "Default")
      (node (ref "J2") (pin "1") (pinfunction "1_1") (pintype "bidirectional"))
      (node (ref "J3") (pin "1") (pinfunction "1_1") (pintype "bidirectional"))
      (node (ref "R44") (pin "2") (pinfunction "2_2") (pintype "passive"))
      (node (ref "U1") (pin "12") (pinfunction "PA05_12") (pintype "bidirectional"))
    )
    (net (code "35") (name "/SCL_5V") (class "Default")
      (node (ref "J1") (pin "1") (pinfunction "1_1") (pintype "bidirectional"))
      (node (ref "R4") (pin "2") (pinfunction "2_2") (pintype "passive"))
      (node (ref "U1") (pin "20") (pinfunction "PB05_20") (pintype "bidirectional"))
    )
    (net (code "36") (name "/SDA") (class "Default")
      (node (ref "J2") (pin "2") (pinfunction "2_2") (pintype "bidirectional"))
      (node (ref "J3") (pin "2") (pinfunction "2_2") (pintype "bidirectional"))
      (node (ref "R43") (pin "2") (pinfunction "2_2") (pintype "passive"))
      (node (ref "U1") (pin "39") (pinfunction "PA17_39") (pintype "bidirectional"))
    )
    (net (code "37") (name "/SDA_5V") (class "Default")
      (node (ref "J1") (pin "2") (pinfunction "2_2") (pintype "bidirectional"))
      (node (ref "R3") (pin "2") (pinfunction "2_2") (pintype "passive"))
      (node (ref "U1") (pin "24") (pinfunction "PA21_24") (pintype "bidirectional"))
    )
    (net (code "38") (name "/SIG_CPU_BATT_CURR") (class "Default")
      (node (ref "R_CURR_MEAS1") (pin "1") (pinfunction "1_1") (pintype "passive"))
      (node (ref "U1") (pin "30") (pinfunction "PB06_30") (pintype "bidirectional"))
    )
    (net (code "39") (name "/SIG_FAN") (class "Default")
      (node (ref "R_PULSE_FAN") (pin "1") (pinfunction "1_1") (pintype "passive"))
      (node (ref "U1") (pin "29") (pinfunction "PB09_29") (pintype "bidirectional"))
    )
    (net (code "40") (name "/SIG_MOT_CURR") (class "Default")
      (node (ref "C_CURR_MEAS3") (pin "1") (pinfunction "1_1") (pintype "passive"))
      (node (ref "R_AMPSET_H") (pin "1") (pinfunction "1_1") (pintype "passive"))
      (node (ref "U1") (pin "37") (pinfunction "PA15_37") (pintype "bidirectional"))
      (node (ref "U2") (pin "1") (pinfunction "VOUT_1") (pintype "output"))
    )
    (net (code "41") (name "/SIG_TEMP_SENS") (class "Default")
      (node (ref "C_TEMP") (pin "1") (pinfunction "1_1") (pintype "passive"))
      (node (ref "R_TEMP_H") (pin "2") (pinfunction "2_2") (pintype "passive"))
      (node (ref "R_TEMP_L") (pin "1") (pinfunction "1_1") (pintype "passive"))
      (node (ref "U1") (pin "32") (pinfunction "PB08_32") (pintype "bidirectional"))
    )
    (net (code "42") (name "/SIG_VMBAT") (class "Default")
      (node (ref "R_VMBAT_S") (pin "2") (pinfunction "2_2") (pintype "passive"))
      (node (ref "U1") (pin "38") (pinfunction "PA16_38") (pintype "bidirectional"))
    )
    (net (code "43") (name "/STATUS_LED") (class "Default")
      (node (ref "R_LED1") (pin "2") (pinfunction "2_2") (pintype "passive"))
      (node (ref "R_LED2") (pin "2") (pinfunction "2_2") (pintype "passive"))
      (node (ref "U1") (pin "25") (pinfunction "PA20_25") (pintype "bidirectional"))
    )
    (net (code "44") (name "/TX_EXT_PIN") (class "Default")
      (node (ref "R_CPU_RX") (pin "2") (pinfunction "2_2") (pintype "passive"))
      (node (ref "U1") (pin "13") (pinfunction "PA02_13") (pintype "bidirectional"))
    )
    (net (code "45") (name "/USB_C_DN") (class "Default")
      (node (ref "SV1") (pin "3") (pinfunction "3_3") (pintype "passive"))
      (node (ref "SV8") (pin "20") (pinfunction "20_20") (pintype "passive"))
      (node (ref "U$17") (pin "1_IO1") (pinfunction "IO1_1_IO1") (pintype "bidirectional"))
    )
    (net (code "46") (name "/USB_C_DP") (class "Default")
      (node (ref "SV1") (pin "1") (pinfunction "1_1") (pintype "passive"))
      (node (ref "SV8") (pin "22") (pinfunction "22_22") (pintype "passive"))
      (node (ref "U$17") (pin "6_IO4") (pinfunction "IO4_6_IO4") (pintype "bidirectional"))
    )
    (net (code "47") (name "/VDDANA") (class "Default")
      (node (ref "C_CURR_MEAS1") (pin "1") (pinfunction "1_1") (pintype "passive"))
      (node (ref "C_VCORE3") (pin "1") (pinfunction "1_1") (pintype "passive"))
      (node (ref "C_VDDANA_BULK") (pin "1") (pinfunction "1_1") (pintype "passive"))
      (node (ref "D2") (pin "C") (pinfunction "C_C") (pintype "passive"))
      (node (ref "L_AVCC1") (pin "2") (pinfunction "2_2") (pintype "passive"))
      (node (ref "U1") (pin "34") (pinfunction "ADVREFP_34") (pintype "input"))
      (node (ref "U1") (pin "35") (pinfunction "VDDANA_35") (pintype "power_in"))
      (node (ref "U2") (pin "5") (pinfunction "VDD_5") (pintype "power_in"))
    )
    (net (code "48") (name "/XTAL1") (class "Default")
      (node (ref "C_XTAL2") (pin "1") (pinfunction "1_1") (pintype "passive"))
      (node (ref "Q2") (pin "1") (pinfunction "1_1") (pintype "passive"))
      (node (ref "U1") (pin "3") (pinfunction "PA08_3") (pintype "bidirectional"))
    )
    (net (code "49") (name "/XTAL2") (class "Default")
      (node (ref "C_XTAL1") (pin "1") (pinfunction "1_1") (pintype "passive"))
      (node (ref "Q2") (pin "2") (pinfunction "2_2") (pintype "passive"))
      (node (ref "U1") (pin "2") (pinfunction "PA09_2") (pintype "bidirectional"))
    )
    (net (code "50") (name "GND") (class "Default")
      (node (ref "C1") (pin "2") (pinfunction "2_2") (pintype "passive"))
      (node (ref "C10") (pin "2") (pinfunction "2_2") (pintype "passive"))
      (node (ref "C15") (pin "2") (pinfunction "2_2") (pintype "passive"))
      (node (ref "C19") (pin "2") (pinfunction "2_2") (pintype "passive"))
      (node (ref "C21") (pin "2") (pinfunction "2_2") (pintype "passive"))
      (node (ref "C22") (pin "2") (pinfunction "2_2") (pintype "passive"))
      (node (ref "C3") (pin "2") (pinfunction "2_2") (pintype "passive"))
      (node (ref "C5") (pin "-") (pinfunction "-_-") (pintype "passive"))
      (node (ref "C_3V3_BULK") (pin "2") (pinfunction "2_2") (pintype "passive"))
      (node (ref "C_AVCC1") (pin "2") (pinfunction "2_2") (pintype "passive"))
      (node (ref "C_CURR_MEAS") (pin "2") (pinfunction "2_2") (pintype "passive"))
      (node (ref "C_CURR_MEAS1") (pin "2") (pinfunction "2_2") (pintype "passive"))
      (node (ref "C_CURR_MEAS2") (pin "2") (pinfunction "2_2") (pintype "passive"))
      (node (ref "C_LDO_IN1") (pin "2") (pinfunction "2_2") (pintype "passive"))
      (node (ref "C_LDO_OUT1") (pin "2") (pinfunction "2_2") (pintype "passive"))
      (node (ref "C_MCU_IN1") (pin "2") (pinfunction "2_2") (pintype "passive"))
      (node (ref "C_MCU_IN2") (pin "2") (pinfunction "2_2") (pintype "passive"))
      (node (ref "C_MCU_IN3") (pin "2") (pinfunction "2_2") (pintype "passive"))
      (node (ref "C_MCU_USB1") (pin "2") (pinfunction "2_2") (pintype "passive"))
      (node (ref "C_TEMP") (pin "2") (pinfunction "2_2") (pintype "passive"))
      (node (ref "C_TWI_3V3") (pin "2") (pinfunction "2_2") (pintype "passive"))
      (node (ref "C_TWI_3V3_2") (pin "2") (pinfunction "2_2") (pintype "passive"))
      (node (ref "C_TWI_5V_BYP") (pin "2") (pinfunction "2_2") (pintype "passive"))
      (node (ref "C_VCORE1") (pin "2") (pinfunction "2_2") (pintype "passive"))
      (node (ref "C_VCORE2") (pin "2") (pinfunction "2_2") (pintype "passive"))
      (node (ref "C_VCORE3") (pin "2") (pinfunction "2_2") (pintype "passive"))
      (node (ref "C_VDDANA_BULK") (pin "2") (pinfunction "2_2") (pintype "passive"))
      (node (ref "C_VDDIO1") (pin "2") (pinfunction "2_2") (pintype "passive"))
      (node (ref "C_VDDIO2") (pin "2") (pinfunction "2_2") (pintype "passive"))
      (node (ref "C_VMBAT") (pin "1") (pinfunction "1_1") (pintype "passive"))
      (node (ref "C_XTAL1") (pin "2") (pinfunction "2_2") (pintype "passive"))
      (node (ref "C_XTAL2") (pin "2") (pinfunction "2_2") (pintype "passive"))
      (node (ref "J1") (pin "4") (pinfunction "4_4") (pintype "bidirectional"))
      (node (ref "J2") (pin "4") (pinfunction "4_4") (pintype "bidirectional"))
      (node (ref "J3") (pin "4") (pinfunction "4_4") (pintype "bidirectional"))
      (node (ref "JP10") (pin "3") (pinfunction "3_3") (pintype "passive"))
      (node (ref "JP12") (pin "1") (pinfunction "1_1") (pintype "passive"))
      (node (ref "JP12") (pin "2") (pinfunction "2_2") (pintype "passive"))
      (node (ref "JP3") (pin "2") (pinfunction "2_2") (pintype "passive"))
      (node (ref "JP4") (pin "1") (pinfunction "1_1") (pintype "passive"))
      (node (ref "JP7") (pin "1") (pinfunction "1_1") (pintype "passive"))
      (node (ref "LED3") (pin "C") (pinfunction "C_C") (pintype "passive"))
      (node (ref "R2") (pin "1") (pinfunction "1_1") (pintype "passive"))
      (node (ref "R7") (pin "2") (pinfunction "2_2") (pintype "passive"))
      (node (ref "R9") (pin "1") (pinfunction "1_1") (pintype "passive"))
      (node (ref "R_AMPSET_L") (pin "1") (pinfunction "1_1") (pintype "passive"))
      (node (ref "R_DRAIN_3V3") (pin "1") (pinfunction "1_1") (pintype "passive"))
      (node (ref "R_MCU_USB1") (pin "2") (pinfunction "2_2") (pintype "passive"))
      (node (ref "R_TEMP_L") (pin "2") (pinfunction "2_2") (pintype "passive"))
      (node (ref "R_VMBAT_L") (pin "1") (pinfunction "1_1") (pintype "passive"))
      (node (ref "SER_PWN_N_PD1") (pin "1") (pinfunction "1_1") (pintype "passive"))
      (node (ref "SER_PWN_N_PD2") (pin "1") (pinfunction "1_1") (pintype "passive"))
      (node (ref "SV1") (pin "4") (pinfunction "4_4") (pintype "passive"))
      (node (ref "SV2") (pin "1") (pinfunction "1_1") (pintype "passive"))
      (node (ref "SV2") (pin "2") (pinfunction "2_2") (pintype "passive"))
      (node (ref "SV5") (pin "3") (pinfunction "3_3") (pintype "passive"))
      (node (ref "SV5") (pin "7") (pinfunction "7_7") (pintype "passive"))
      (node (ref "SV6") (pin "3") (pinfunction "3_3") (pintype "passive"))
      (node (ref "SV7") (pin "1") (pinfunction "1_1") (pintype "passive"))
      (node (ref "SV8") (pin "9") (pinfunction "9_9") (pintype "passive"))
      (node (ref "U$13") (pin "3") (pinfunction "GND_3") (pintype "passive"))
      (node (ref "U$16") (pin "GND") (pinfunction "GND_GND") (pintype "bidirectional"))
      (node (ref "U$2") (pin "1") (pinfunction "GND_1") (pintype "passive"))
      (node (ref "U$4") (pin "2") (pinfunction "GND_2") (pintype "bidirectional"))
      (node (ref "U$5") (pin "5") (pinfunction "S1_5") (pintype "bidirectional"))
      (node (ref "U$6") (pin "5") (pinfunction "S1_5") (pintype "bidirectional"))
      (node (ref "U$7") (pin "4") (pinfunction "GND_4") (pintype "bidirectional"))
      (node (ref "U$8") (pin "4") (pinfunction "GND_4") (pintype "bidirectional"))
      (node (ref "U$9") (pin "4") (pinfunction "GND_4") (pintype "bidirectional"))
      (node (ref "U1") (pin "1") (pinfunction "GND_4_1") (pintype "passive"))
      (node (ref "U1") (pin "19") (pinfunction "GND_2_19") (pintype "passive"))
      (node (ref "U1") (pin "33") (pinfunction "GNDANA_33") (pintype "passive"))
      (node (ref "U1") (pin "43") (pinfunction "GND_43") (pintype "passive"))
      (node (ref "U1") (pin "45") (pinfunction "GND_3_45") (pintype "passive"))
      (node (ref "U2") (pin "2") (pinfunction "VSS_2") (pintype "passive"))
    )
    (net (code "51") (name "Net-(C10-Pad1)") (class "Default")
      (node (ref "C10") (pin "1") (pinfunction "1_1") (pintype "passive"))
      (node (ref "L_TSR1") (pin "2") (pinfunction "2_2") (pintype "passive"))
      (node (ref "U$16") (pin "IN") (pinfunction "IN_IN") (pintype "bidirectional"))
    )
    (net (code "52") (name "Net-(C22-Pad1)") (class "Default")
      (node (ref "C22") (pin "1") (pinfunction "1_1") (pintype "passive"))
      (node (ref "R5") (pin "1") (pinfunction "1_1") (pintype "passive"))
      (node (ref "R6") (pin "1") (pinfunction "1_1") (pintype "passive"))
      (node (ref "R7") (pin "1") (pinfunction "1_1") (pintype "passive"))
    )
    (net (code "53") (name "Net-(C_CURR_MEAS-Pad1)") (class "Default")
      (node (ref "C_CURR_MEAS") (pin "1") (pinfunction "1_1") (pintype "passive"))
      (node (ref "R_CURR_MEAS") (pin "1") (pinfunction "1_1") (pintype "passive"))
      (node (ref "R_CURR_MEAS1") (pin "2") (pinfunction "2_2") (pintype "passive"))
    )
    (net (code "54") (name "Net-(C_VCORE2-Pad1)") (class "Default")
      (node (ref "C_VCORE2") (pin "1") (pinfunction "1_1") (pintype "passive"))
      (node (ref "R_VCORE") (pin "1") (pinfunction "1_1") (pintype "passive"))
    )
    (net (code "55") (name "Net-(C_VMBAT-Pad2)") (class "Default")
      (node (ref "C_VMBAT") (pin "2") (pinfunction "2_2") (pintype "passive"))
      (node (ref "R_VMBAT_H") (pin "1") (pinfunction "1_1") (pintype "passive"))
      (node (ref "R_VMBAT_L") (pin "2") (pinfunction "2_2") (pintype "passive"))
      (node (ref "R_VMBAT_S") (pin "1") (pinfunction "1_1") (pintype "passive"))
    )
    (net (code "56") (name "Net-(LED1-PadC)") (class "Default")
      (node (ref "LED1") (pin "C") (pinfunction "C_C") (pintype "passive"))
      (node (ref "R1") (pin "2") (pinfunction "2_2") (pintype "passive"))
    )
    (net (code "57") (name "Net-(LED2-PadC)") (class "Default")
      (node (ref "LED2") (pin "C") (pinfunction "C_C") (pintype "passive"))
      (node (ref "R_LED1") (pin "1") (pinfunction "1_1") (pintype "passive"))
    )
    (net (code "58") (name "Net-(LED3-PadA)") (class "Default")
      (node (ref "LED3") (pin "A") (pinfunction "A_A") (pintype "passive"))
      (node (ref "R_LED2") (pin "1") (pinfunction "1_1") (pintype "passive"))
    )
    (net (code "59") (name "Net-(LED4-PadC)") (class "Default")
      (node (ref "LED4") (pin "C") (pinfunction "C_C") (pintype "passive"))
      (node (ref "R27") (pin "2") (pinfunction "2_2") (pintype "passive"))
    )
    (net (code "60") (name "Net-(LED12-PadC)") (class "Default")
      (node (ref "LED12") (pin "C") (pinfunction "C_C") (pintype "passive"))
      (node (ref "R2") (pin "2") (pinfunction "2_2") (pintype "passive"))
    )
    (net (code "61") (name "Net-(Q1-G)") (class "Default")
      (node (ref "C_PB_BYPASS") (pin "1") (pinfunction "1_1") (pintype "passive"))
      (node (ref "D_PB_ZENER") (pin "1") (pinfunction "1_1") (pintype "passive"))
      (node (ref "Q1") (pin "1") (pinfunction "G_1") (pintype "passive"))
      (node (ref "R_PB_PD") (pin "1") (pinfunction "1_1") (pintype "passive"))
      (node (ref "R_PB_PU") (pin "2") (pinfunction "2_2") (pintype "passive"))
    )
    (net (code "62") (name "Net-(Q1-S)") (class "Default")
      (node (ref "C_PB_BYPASS") (pin "2") (pinfunction "2_2") (pintype "passive"))
      (node (ref "D_PB_ZENER") (pin "2") (pinfunction "2_2") (pintype "passive"))
      (node (ref "Q1") (pin "2") (pinfunction "S_2") (pintype "passive"))
      (node (ref "R27") (pin "1") (pinfunction "1_1") (pintype "passive"))
      (node (ref "R_PB_PU") (pin "1") (pinfunction "1_1") (pintype "passive"))
      (node (ref "U$15") (pin "P$1") (pinfunction "1_P$1") (pintype "bidirectional"))
    )
    (net (code "63") (name "Net-(Q3-D)") (class "Default")
      (node (ref "Q3") (pin "3") (pinfunction "D_3") (pintype "passive"))
      (node (ref "SV6") (pin "2") (pinfunction "2_2") (pintype "passive"))
    )
    (net (code "64") (name "Net-(Q3-G)") (class "Default")
      (node (ref "Q3") (pin "1") (pinfunction "G_1") (pintype "passive"))
      (node (ref "R15") (pin "1") (pinfunction "1_1") (pintype "passive"))
    )
    (net (code "65") (name "Net-(R_AUX_UART_RX-Pad1)") (class "Default")
      (node (ref "R_AUX_UART_RX") (pin "1") (pinfunction "1_1") (pintype "passive"))
      (node (ref "SV2") (pin "5") (pinfunction "5_5") (pintype "passive"))
    )
    (net (code "66") (name "Net-(R_AUX_UART_TX-Pad1)") (class "Default")
      (node (ref "R_AUX_UART_TX") (pin "1") (pinfunction "1_1") (pintype "passive"))
      (node (ref "SV2") (pin "6") (pinfunction "6_6") (pintype "passive"))
    )
    (net (code "67") (name "Net-(R_CPU_RX-Pad1)") (class "Default")
      (node (ref "R_CPU_RX") (pin "1") (pinfunction "1_1") (pintype "passive"))
      (node (ref "SV8") (pin "24") (pinfunction "24_24") (pintype "passive"))
    )
    (net (code "68") (name "Net-(R_CPU_TX-Pad2)") (class "Default")
      (node (ref "R_CPU_TX") (pin "2") (pinfunction "2_2") (pintype "passive"))
      (node (ref "SV8") (pin "23") (pinfunction "23_23") (pintype "passive"))
    )
    (net (code "69") (name "Net-(R_PULSE_FAN-Pad2)") (class "Default")
      (node (ref "R_PULSE_FAN") (pin "2") (pinfunction "2_2") (pintype "passive"))
      (node (ref "R_PULSE_FAN1") (pin "2") (pinfunction "2_2") (pintype "passive"))
      (node (ref "SV6") (pin "1") (pinfunction "1_1") (pintype "passive"))
    )
    (net (code "70") (name "Net-(U$1-OUT1)") (class "Default")
      (node (ref "SV3") (pin "1") (pinfunction "1_1") (pintype "passive"))
      (node (ref "U$1") (pin "P$10") (pinfunction "OUT1_P$10") (pintype "bidirectional"))
      (node (ref "U$1") (pin "P$8") (pinfunction "OUT3_P$8") (pintype "bidirectional"))
    )
    (net (code "71") (name "Net-(U$1-OUT2)") (class "Default")
      (node (ref "SV3") (pin "2") (pinfunction "2_2") (pintype "passive"))
      (node (ref "U$1") (pin "P$7") (pinfunction "OUT4_P$7") (pintype "bidirectional"))
      (node (ref "U$1") (pin "P$9") (pinfunction "OUT2_P$9") (pintype "bidirectional"))
    )
    (net (code "72") (name "Net-(U$3-OUT1)") (class "Default")
      (node (ref "SV4") (pin "1") (pinfunction "1_1") (pintype "passive"))
      (node (ref "U$3") (pin "P$10") (pinfunction "OUT1_P$10") (pintype "bidirectional"))
      (node (ref "U$3") (pin "P$8") (pinfunction "OUT3_P$8") (pintype "bidirectional"))
    )
    (net (code "73") (name "Net-(U$3-OUT2)") (class "Default")
      (node (ref "SV4") (pin "2") (pinfunction "2_2") (pintype "passive"))
      (node (ref "U$3") (pin "P$7") (pinfunction "OUT4_P$7") (pintype "bidirectional"))
      (node (ref "U$3") (pin "P$9") (pinfunction "OUT2_P$9") (pintype "bidirectional"))
    )
    (net (code "74") (name "Net-(U$4-VOUT)") (class "Default")
      (node (ref "R_CURR_MEAS") (pin "2") (pinfunction "2_2") (pintype "passive"))
      (node (ref "U$4") (pin "3") (pinfunction "VOUT_3") (pintype "bidirectional"))
    )
    (net (code "75") (name "Net-(U$5-G1)") (class "Default")
      (node (ref "C19") (pin "1") (pinfunction "1_1") (pintype "passive"))
      (node (ref "SER_PWN_N_PD4") (pin "1") (pinfunction "1_1") (pintype "passive"))
      (node (ref "U$5") (pin "1") (pinfunction "G1_1") (pintype "bidirectional"))
    )
    (net (code "76") (name "Net-(U$5-G2)") (class "Default")
      (node (ref "SER_PWR_P_PU2") (pin "1") (pinfunction "1_1") (pintype "passive"))
      (node (ref "SER_PWR_P_R2") (pin "1") (pinfunction "1_1") (pintype "passive"))
      (node (ref "U$5") (pin "3") (pinfunction "G2_3") (pintype "bidirectional"))
    )
    (net (code "77") (name "Net-(U$6-G1)") (class "Default")
      (node (ref "C21") (pin "1") (pinfunction "1_1") (pintype "passive"))
      (node (ref "SER_PWN_N_PD3") (pin "1") (pinfunction "1_1") (pintype "passive"))
      (node (ref "U$6") (pin "1") (pinfunction "G1_1") (pintype "bidirectional"))
    )
    (net (code "78") (name "Net-(U$6-G2)") (class "Default")
      (node (ref "C20") (pin "2") (pinfunction "2_2") (pintype "passive"))
      (node (ref "SER_PWR_P_R1") (pin "1") (pinfunction "1_1") (pintype "passive"))
      (node (ref "U$6") (pin "3") (pinfunction "G2_3") (pintype "bidirectional"))
    )
    (net (code "79") (name "Net-(U$7-OUT1)") (class "Default")
      (node (ref "R_PB_PD") (pin "2") (pinfunction "2_2") (pintype "passive"))
      (node (ref "U$7") (pin "1") (pinfunction "OUT1_1") (pintype "bidirectional"))
    )
    (net (code "80") (name "Net-(U$8-OUT2)") (class "Default")
      (node (ref "R14") (pin "1") (pinfunction "1_1") (pintype "passive"))
      (node (ref "R15") (pin "2") (pinfunction "2_2") (pintype "passive"))
      (node (ref "U$8") (pin "2") (pinfunction "OUT2_2") (pintype "bidirectional"))
    )
    (net (code "81") (name "Net-(U$13-VOUT)") (class "Default")
      (node (ref "R_TEMP_H") (pin "1") (pinfunction "1_1") (pintype "passive"))
      (node (ref "U$13") (pin "2") (pinfunction "VOUT_2") (pintype "output"))
    )
    (net (code "82") (name "Net-(U$14-1)") (class "Default")
      (node (ref "JP1") (pin "1") (pinfunction "1_1") (pintype "passive"))
      (node (ref "U$14") (pin "P$1") (pinfunction "1_P$1") (pintype "bidirectional"))
    )
    (net (code "83") (name "Net-(U$17-GND)") (class "Default")
      (node (ref "C_MCU_USB1") (pin "1") (pinfunction "1_1") (pintype "passive"))
      (node (ref "R_MCU_USB1") (pin "1") (pinfunction "1_1") (pintype "passive"))
      (node (ref "SV1") (pin "5") (pinfunction "5_5") (pintype "passive"))
      (node (ref "SV1") (pin "6") (pinfunction "6_6") (pintype "passive"))
      (node (ref "U$17") (pin "2_GND") (pinfunction "GND_2_GND") (pintype "bidirectional"))
    )
    (net (code "84") (name "Net-(U1-VDDCORE)") (class "Default")
      (node (ref "C_VCORE1") (pin "1") (pinfunction "1_1") (pintype "passive"))
      (node (ref "L_AVCC1") (pin "1") (pinfunction "1_1") (pintype "passive"))
      (node (ref "R_VCORE") (pin "2") (pinfunction "2_2") (pintype "passive"))
      (node (ref "U1") (pin "18") (pinfunction "VDDCORE_18") (pintype "power_in"))
    )
    (net (code "85") (name "Net-(U2-VIN+)") (class "Default")
      (node (ref "C_CURR_MEAS2") (pin "1") (pinfunction "1_1") (pintype "passive"))
      (node (ref "D2") (pin "A") (pinfunction "A_A") (pintype "passive"))
      (node (ref "R10") (pin "1") (pinfunction "1_1") (pintype "passive"))
      (node (ref "U2") (pin "3") (pinfunction "VIN+_3") (pintype "input"))
    )
    (net (code "86") (name "Net-(U2-VIN-)") (class "Default")
      (node (ref "C_CURR_MEAS3") (pin "2") (pinfunction "2_2") (pintype "passive"))
      (node (ref "R_AMPSET_H") (pin "2") (pinfunction "2_2") (pintype "passive"))
      (node (ref "R_AMPSET_L") (pin "2") (pinfunction "2_2") (pintype "passive"))
      (node (ref "U2") (pin "4") (pinfunction "VIN-_4") (pintype "input"))
    )
    (net (code "87") (name "unconnected-(JP2-Pad1)") (class "Default")
      (node (ref "JP2") (pin "1") (pinfunction "1_1") (pintype "passive"))
    )
    (net (code "88") (name "unconnected-(JP2-Pad2)") (class "Default")
      (node (ref "JP2") (pin "2") (pinfunction "2_2") (pintype "passive"))
    )
    (net (code "89") (name "unconnected-(JP5-Pad1)") (class "Default")
      (node (ref "JP5") (pin "1") (pinfunction "1_1") (pintype "passive"))
    )
    (net (code "90") (name "unconnected-(JP8-Pad1)") (class "Default")
      (node (ref "JP8") (pin "1") (pinfunction "1_1") (pintype "passive"))
    )
    (net (code "91") (name "unconnected-(JP9-Pad1)") (class "Default")
      (node (ref "JP9") (pin "1") (pinfunction "1_1") (pintype "passive"))
    )
    (net (code "92") (name "unconnected-(JP11-Pad1)") (class "Default")
      (node (ref "JP11") (pin "1") (pinfunction "1_1") (pintype "passive"))
    )
    (net (code "93") (name "unconnected-(JP13-Pad1)") (class "Default")
      (node (ref "JP13") (pin "1") (pinfunction "1_1") (pintype "passive"))
    )
    (net (code "94") (name "unconnected-(JP14-Pad1)") (class "Default")
      (node (ref "JP14") (pin "1") (pinfunction "1_1") (pintype "passive"))
    )
    (net (code "95") (name "unconnected-(JP15-Pad1)") (class "Default")
      (node (ref "JP15") (pin "1") (pinfunction "1_1") (pintype "passive"))
    )
    (net (code "96") (name "unconnected-(JP16-Pad1)") (class "Default")
      (node (ref "JP16") (pin "1") (pinfunction "1_1") (pintype "passive"))
    )
    (net (code "97") (name "unconnected-(S2-P$1-PadP1)") (class "Default")
      (node (ref "S2") (pin "P1") (pinfunction "P$1_P1") (pintype "bidirectional"))
    )
    (net (code "98") (name "unconnected-(S3-P$1-PadP1)") (class "Default")
      (node (ref "S3") (pin "P1") (pinfunction "P$1_P1") (pintype "bidirectional"))
    )
    (net (code "99") (name "unconnected-(SV8-Pad2)") (class "Default")
      (node (ref "SV8") (pin "2") (pinfunction "2_2") (pintype "passive"))
    )
    (net (code "100") (name "unconnected-(SV8-Pad3)") (class "Default")
      (node (ref "SV8") (pin "3") (pinfunction "3_3") (pintype "passive"))
    )
    (net (code "101") (name "unconnected-(SV8-Pad4)") (class "Default")
      (node (ref "SV8") (pin "4") (pinfunction "4_4") (pintype "passive"))
    )
    (net (code "102") (name "unconnected-(SV8-Pad5)") (class "Default")
      (node (ref "SV8") (pin "5") (pinfunction "5_5") (pintype "passive"))
    )
    (net (code "103") (name "unconnected-(SV8-Pad6)") (class "Default")
      (node (ref "SV8") (pin "6") (pinfunction "6_6") (pintype "passive"))
    )
    (net (code "104") (name "unconnected-(SV8-Pad7)") (class "Default")
      (node (ref "SV8") (pin "7") (pinfunction "7_7") (pintype "passive"))
    )
    (net (code "105") (name "unconnected-(SV8-Pad8)") (class "Default")
      (node (ref "SV8") (pin "8") (pinfunction "8_8") (pintype "passive"))
    )
    (net (code "106") (name "unconnected-(SV8-Pad10)") (class "Default")
      (node (ref "SV8") (pin "10") (pinfunction "10_10") (pintype "passive"))
    )
    (net (code "107") (name "unconnected-(SV8-Pad11)") (class "Default")
      (node (ref "SV8") (pin "11") (pinfunction "11_11") (pintype "passive"))
    )
    (net (code "108") (name "unconnected-(SV8-Pad12)") (class "Default")
      (node (ref "SV8") (pin "12") (pinfunction "12_12") (pintype "passive"))
    )
    (net (code "109") (name "unconnected-(SV8-Pad13)") (class "Default")
      (node (ref "SV8") (pin "13") (pinfunction "13_13") (pintype "passive"))
    )
    (net (code "110") (name "unconnected-(SV8-Pad14)") (class "Default")
      (node (ref "SV8") (pin "14") (pinfunction "14_14") (pintype "passive"))
    )
    (net (code "111") (name "unconnected-(SV8-Pad15)") (class "Default")
      (node (ref "SV8") (pin "15") (pinfunction "15_15") (pintype "passive"))
    )
    (net (code "112") (name "unconnected-(SV8-Pad16)") (class "Default")
      (node (ref "SV8") (pin "16") (pinfunction "16_16") (pintype "passive"))
    )
    (net (code "113") (name "unconnected-(SV8-Pad17)") (class "Default")
      (node (ref "SV8") (pin "17") (pinfunction "17_17") (pintype "passive"))
    )
    (net (code "114") (name "unconnected-(SV8-Pad18)") (class "Default")
      (node (ref "SV8") (pin "18") (pinfunction "18_18") (pintype "passive"))
    )
    (net (code "115") (name "unconnected-(SV8-Pad19)") (class "Default")
      (node (ref "SV8") (pin "19") (pinfunction "19_19") (pintype "passive"))
    )
    (net (code "116") (name "unconnected-(SV8-Pad21)") (class "Default")
      (node (ref "SV8") (pin "21") (pinfunction "21_21") (pintype "passive"))
    )
    (net (code "117") (name "unconnected-(SV8-Pad25)") (class "Default")
      (node (ref "SV8") (pin "25") (pinfunction "25_25") (pintype "passive"))
    )
    (net (code "118") (name "unconnected-(SV8-Pad26)") (class "Default")
      (node (ref "SV8") (pin "26") (pinfunction "26_26") (pintype "passive"))
    )
    (net (code "119") (name "unconnected-(SV8-Pad27)") (class "Default")
      (node (ref "SV8") (pin "27") (pinfunction "27_27") (pintype "passive"))
    )
    (net (code "120") (name "unconnected-(SV8-Pad28)") (class "Default")
      (node (ref "SV8") (pin "28") (pinfunction "28_28") (pintype "passive"))
    )
    (net (code "121") (name "unconnected-(SV8-Pad29)") (class "Default")
      (node (ref "SV8") (pin "29") (pinfunction "29_29") (pintype "passive"))
    )
    (net (code "122") (name "unconnected-(SV8-Pad30)") (class "Default")
      (node (ref "SV8") (pin "30") (pinfunction "30_30") (pintype "passive"))
    )
    (net (code "123") (name "unconnected-(SV8-Pad31)") (class "Default")
      (node (ref "SV8") (pin "31") (pinfunction "31_31") (pintype "passive"))
    )
    (net (code "124") (name "unconnected-(SV8-Pad32)") (class "Default")
      (node (ref "SV8") (pin "32") (pinfunction "32_32") (pintype "passive"))
    )
    (net (code "125") (name "unconnected-(SV8-Pad33)") (class "Default")
      (node (ref "SV8") (pin "33") (pinfunction "33_33") (pintype "passive"))
    )
    (net (code "126") (name "unconnected-(SV8-Pad34)") (class "Default")
      (node (ref "SV8") (pin "34") (pinfunction "34_34") (pintype "passive"))
    )
    (net (code "127") (name "unconnected-(SV8-Pad35)") (class "Default")
      (node (ref "SV8") (pin "35") (pinfunction "35_35") (pintype "passive"))
    )
    (net (code "128") (name "unconnected-(SV8-Pad36)") (class "Default")
      (node (ref "SV8") (pin "36") (pinfunction "36_36") (pintype "passive"))
    )
    (net (code "129") (name "unconnected-(SV8-Pad37)") (class "Default")
      (node (ref "SV8") (pin "37") (pinfunction "37_37") (pintype "passive"))
    )
    (net (code "130") (name "unconnected-(SV8-Pad38)") (class "Default")
      (node (ref "SV8") (pin "38") (pinfunction "38_38") (pintype "passive"))
    )
    (net (code "131") (name "unconnected-(SV8-Pad39)") (class "Default")
      (node (ref "SV8") (pin "39") (pinfunction "39_39") (pintype "passive"))
    )
    (net (code "132") (name "unconnected-(SV8-Pad40)") (class "Default")
      (node (ref "SV8") (pin "40") (pinfunction "40_40") (pintype "passive"))
    )
    (net (code "133") (name "unconnected-(U$7-IN2-Pad3)") (class "Default")
      (node (ref "U$7") (pin "3") (pinfunction "IN2_3") (pintype "bidirectional"))
    )
    (net (code "134") (name "unconnected-(U$7-OUT2-Pad2)") (class "Default")
      (node (ref "U$7") (pin "2") (pinfunction "OUT2_2") (pintype "bidirectional"))
    )
    (net (code "135") (name "unconnected-(U$8-IN1-Pad5)") (class "Default")
      (node (ref "U$8") (pin "5") (pinfunction "IN1_5") (pintype "bidirectional"))
    )
    (net (code "136") (name "unconnected-(U$8-OUT1-Pad1)") (class "Default")
      (node (ref "U$8") (pin "1") (pinfunction "OUT1_1") (pintype "bidirectional"))
    )
    (net (code "137") (name "unconnected-(U$17-IO2-Pad3_IO2)") (class "Default")
      (node (ref "U$17") (pin "3_IO2") (pinfunction "IO2_3_IO2") (pintype "bidirectional"))
    )
    (net (code "138") (name "unconnected-(U$17-IO3-Pad4_IO3)") (class "Default")
      (node (ref "U$17") (pin "4_IO3") (pinfunction "IO3_4_IO3") (pintype "bidirectional"))
    )
    (net (code "139") (name "unconnected-(U1-PA01-Pad14)") (class "Default")
      (node (ref "U1") (pin "14") (pinfunction "PA01_14") (pintype "bidirectional"))
    )
    (net (code "140") (name "unconnected-(U1-PA03-Pad4)") (class "Default")
      (node (ref "U1") (pin "4") (pinfunction "PA03_4") (pintype "bidirectional"))
    )
    (net (code "141") (name "unconnected-(U1-PB00-Pad6)") (class "Default")
      (node (ref "U1") (pin "6") (pinfunction "PB00_6") (pintype "bidirectional"))
    )
    (net (code "142") (name "unconnected-(U1-PB01-Pad16)") (class "Default")
      (node (ref "U1") (pin "16") (pinfunction "PB01_16") (pintype "bidirectional"))
    )
    (net (code "143") (name "unconnected-(U1-PB04-Pad21)") (class "Default")
      (node (ref "U1") (pin "21") (pinfunction "PB04_21") (pintype "bidirectional"))
    )
    (net (code "144") (name "unconnected-(U1-PB10-Pad23)") (class "Default")
      (node (ref "U1") (pin "23") (pinfunction "PB10_23") (pintype "bidirectional"))
    )
    (net (code "145") (name "unconnected-(U1-PB12-Pad5)") (class "Default")
      (node (ref "U1") (pin "5") (pinfunction "PB12_5") (pintype "bidirectional"))
    )
  )
)
